# alphanewt_v1_7.net
KiCad netlist of a schematic drawn in EAGLE
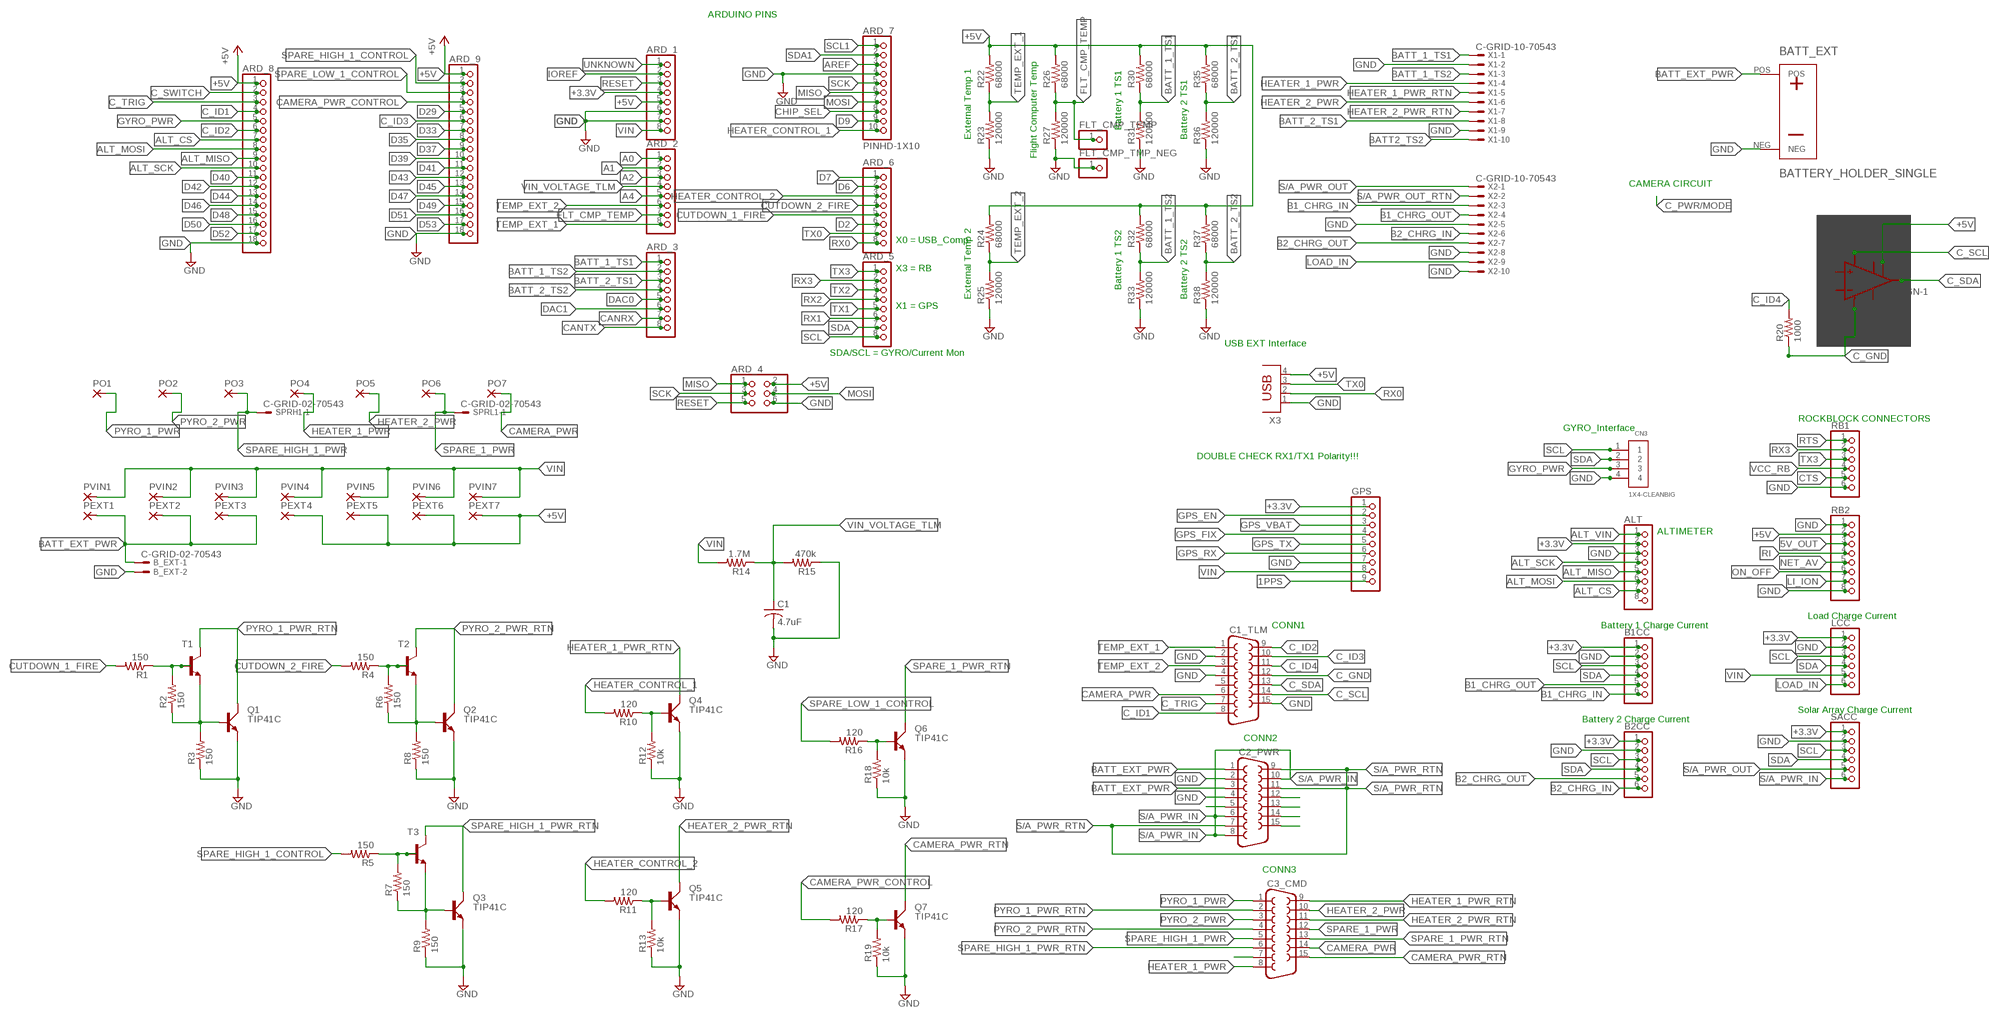
[diagram p0: schematic, sheet 1]

(export (version "E")
  (design (tool "Eeschema 10.0.6"))
  (components
    (comp (ref "ALT")
      (value "PINHD-1X8BIG")
      (footprint "eagle-import:1X08-BIG")
      (libsource (lib "eagle-import") (part "PINHD-1X8BIG"))
    )
    (comp (ref "ARD_1")
      (value "PINHD-1X8BIG")
      (footprint "eagle-import:1X08-BIG")
      (libsource (lib "eagle-import") (part "PINHD-1X8BIG"))
    )
    (comp (ref "ARD_2")
      (value "PINHD-1X8BIG")
      (footprint "eagle-import:1X08-BIG")
      (libsource (lib "eagle-import") (part "PINHD-1X8BIG"))
    )
    (comp (ref "ARD_3")
      (value "PINHD-1X8BIG")
      (footprint "eagle-import:1X08-BIG")
      (libsource (lib "eagle-import") (part "PINHD-1X8BIG"))
    )
    (comp (ref "ARD_4")
      (value "PINHD-2X3")
      (footprint "eagle-import:2X03")
      (libsource (lib "eagle-import") (part "PINHD-2X3"))
    )
    (comp (ref "ARD_5")
      (value "PINHD-1X8BIG")
      (footprint "eagle-import:1X08-BIG")
      (libsource (lib "eagle-import") (part "PINHD-1X8BIG"))
    )
    (comp (ref "ARD_6")
      (value "PINHD-1X8BIG")
      (footprint "eagle-import:1X08-BIG")
      (libsource (lib "eagle-import") (part "PINHD-1X8BIG"))
    )
    (comp (ref "ARD_7")
      (value "PINHD-1X10")
      (footprint "eagle-import:1X10-BIG")
      (libsource (lib "eagle-import") (part "PINHD-1X10"))
    )
    (comp (ref "ARD_8")
      (value "PINHD-1X18-BIG")
      (footprint "eagle-import:1X18-BIG")
      (libsource (lib "eagle-import") (part "PINHD-1X18-BIG"))
    )
    (comp (ref "ARD_9")
      (value "PINHD-1X18-BIG")
      (footprint "eagle-import:1X18-BIG")
      (libsource (lib "eagle-import") (part "PINHD-1X18-BIG"))
    )
    (comp (ref "B1CC")
      (value "PINHD-1X6B")
      (footprint "eagle-import:1X06-BIG")
      (libsource (lib "eagle-import") (part "PINHD-1X6B"))
    )
    (comp (ref "B2CC")
      (value "PINHD-1X6B")
      (footprint "eagle-import:1X06-BIG")
      (libsource (lib "eagle-import") (part "PINHD-1X6B"))
    )
    (comp (ref "BATT_EXT")
      (value "BATTERY_HOLDER_SINGLE")
      (footprint "eagle-import:BATT_HOLDER_SINGLE")
      (libsource (lib "eagle-import") (part "BATTERY_HOLDER_SINGLE"))
    )
    (comp (ref "B_EXT")
      (value "C-GRID-02-70543")
      (footprint "eagle-import:70543-02")
      (fields
        (field (name "MF") "MOLEX")
        (field (name "MPN") "70543-0001")
        (field (name "OC_NEWARK") "59H2645")
      )
      (libsource (lib "eagle-import") (part "C-GRID-02-70543"))
    )
    (comp (ref "C1")
      (value "4.7uF")
      (footprint "eagle-import:C0805K")
      (fields (field (name "MPN") "C2012X6S1H475K125AC"))
      (libsource (lib "eagle-import") (part "C-USC0805K"))
    )
    (comp (ref "C1_TLM")
      (value "F15HP")
      (footprint "eagle-import:F15HP")
      (fields (field (name "MPN") "5504F1-15S-02A-03"))
      (libsource (lib "eagle-import") (part "F15HP"))
    )
    (comp (ref "C2_PWR")
      (value "F15HP")
      (footprint "eagle-import:F15HP")
      (fields (field (name "MPN") "5504F1-15S-02A-03"))
      (libsource (lib "eagle-import") (part "F15HP"))
    )
    (comp (ref "C3_CMD")
      (value "F15HP")
      (footprint "eagle-import:F15HP")
      (fields (field (name "MPN") "5504F1-15S-02A-03"))
      (libsource (lib "eagle-import") (part "F15HP"))
    )
    (comp (ref "CN3")
      (value "1X4-CLEANBIG")
      (footprint "eagle-import:1X04-CLEANBIG")
      (libsource (lib "eagle-import") (part "1X4-CLEANBIG"))
    )
    (comp (ref "FLT_CMP_TEMP")
      (value "PINHD-1X1")
      (footprint "eagle-import:1X01")
      (libsource (lib "eagle-import") (part "PINHD-1X1"))
    )
    (comp (ref "FLT_CMP_TMP_NEG")
      (value "PINHD-1X1")
      (footprint "eagle-import:1X01")
      (libsource (lib "eagle-import") (part "PINHD-1X1"))
    )
    (comp (ref "GPS")
      (value "PINHD-1X9")
      (footprint "eagle-import:1X09-BIG")
      (libsource (lib "eagle-import") (part "PINHD-1X9"))
    )
    (comp (ref "IC1")
      (value "LM386N-1")
      (footprint "eagle-import:DIL08")
      (libsource (lib "eagle-import") (part "LM386?-N1"))
    )
    (comp (ref "LCC")
      (value "PINHD-1X6B")
      (footprint "eagle-import:1X06-BIG")
      (libsource (lib "eagle-import") (part "PINHD-1X6B"))
    )
    (comp (ref "PEXT1")
      (value "SMD2")
      (footprint "eagle-import:SMD1,27-2,54")
      (libsource (lib "eagle-import") (part "SMD2"))
    )
    (comp (ref "PEXT2")
      (value "SMD2")
      (footprint "eagle-import:SMD1,27-2,54")
      (libsource (lib "eagle-import") (part "SMD2"))
    )
    (comp (ref "PEXT3")
      (value "SMD2")
      (footprint "eagle-import:SMD1,27-2,54")
      (libsource (lib "eagle-import") (part "SMD2"))
    )
    (comp (ref "PEXT4")
      (value "SMD2")
      (footprint "eagle-import:SMD1,27-2,54")
      (libsource (lib "eagle-import") (part "SMD2"))
    )
    (comp (ref "PEXT5")
      (value "SMD2")
      (footprint "eagle-import:SMD1,27-2,54")
      (libsource (lib "eagle-import") (part "SMD2"))
    )
    (comp (ref "PEXT6")
      (value "SMD2")
      (footprint "eagle-import:SMD1,27-2,54")
      (libsource (lib "eagle-import") (part "SMD2"))
    )
    (comp (ref "PEXT7")
      (value "SMD2")
      (footprint "eagle-import:SMD1,27-2,54")
      (libsource (lib "eagle-import") (part "SMD2"))
    )
    (comp (ref "PO1")
      (value "SMD2")
      (footprint "eagle-import:SMD1,27-2,54")
      (libsource (lib "eagle-import") (part "SMD2"))
    )
    (comp (ref "PO2")
      (value "SMD2")
      (footprint "eagle-import:SMD1,27-2,54")
      (libsource (lib "eagle-import") (part "SMD2"))
    )
    (comp (ref "PO3")
      (value "SMD2")
      (footprint "eagle-import:SMD1,27-2,54")
      (libsource (lib "eagle-import") (part "SMD2"))
    )
    (comp (ref "PO4")
      (value "SMD2")
      (footprint "eagle-import:SMD1,27-2,54")
      (libsource (lib "eagle-import") (part "SMD2"))
    )
    (comp (ref "PO5")
      (value "SMD2")
      (footprint "eagle-import:SMD1,27-2,54")
      (libsource (lib "eagle-import") (part "SMD2"))
    )
    (comp (ref "PO6")
      (value "SMD2")
      (footprint "eagle-import:SMD1,27-2,54")
      (libsource (lib "eagle-import") (part "SMD2"))
    )
    (comp (ref "PO7")
      (value "SMD2")
      (footprint "eagle-import:SMD1,27-2,54")
      (libsource (lib "eagle-import") (part "SMD2"))
    )
    (comp (ref "PVIN1")
      (value "SMD2")
      (footprint "eagle-import:SMD1,27-2,54")
      (libsource (lib "eagle-import") (part "SMD2"))
    )
    (comp (ref "PVIN2")
      (value "SMD2")
      (footprint "eagle-import:SMD1,27-2,54")
      (libsource (lib "eagle-import") (part "SMD2"))
    )
    (comp (ref "PVIN3")
      (value "SMD2")
      (footprint "eagle-import:SMD1,27-2,54")
      (libsource (lib "eagle-import") (part "SMD2"))
    )
    (comp (ref "PVIN4")
      (value "SMD2")
      (footprint "eagle-import:SMD1,27-2,54")
      (libsource (lib "eagle-import") (part "SMD2"))
    )
    (comp (ref "PVIN5")
      (value "SMD2")
      (footprint "eagle-import:SMD1,27-2,54")
      (libsource (lib "eagle-import") (part "SMD2"))
    )
    (comp (ref "PVIN6")
      (value "SMD2")
      (footprint "eagle-import:SMD1,27-2,54")
      (libsource (lib "eagle-import") (part "SMD2"))
    )
    (comp (ref "PVIN7")
      (value "SMD2")
      (footprint "eagle-import:SMD1,27-2,54")
      (libsource (lib "eagle-import") (part "SMD2"))
    )
    (comp (ref "Q1")
      (value "TIP41C")
      (footprint "eagle-import:TO220AV")
      (fields (field (name "MF") "FAIRCHILD SEMICONDUCTOR"))
      (libsource (lib "eagle-import") (part "TIP41C"))
    )
    (comp (ref "Q2")
      (value "TIP41C")
      (footprint "eagle-import:TO220AV")
      (fields (field (name "MF") "FAIRCHILD SEMICONDUCTOR"))
      (libsource (lib "eagle-import") (part "TIP41C"))
    )
    (comp (ref "Q3")
      (value "TIP41C")
      (footprint "eagle-import:TO220AV")
      (fields (field (name "MF") "FAIRCHILD SEMICONDUCTOR"))
      (libsource (lib "eagle-import") (part "TIP41C"))
    )
    (comp (ref "Q4")
      (value "TIP41C")
      (footprint "eagle-import:TO220AV")
      (fields (field (name "MF") "FAIRCHILD SEMICONDUCTOR"))
      (libsource (lib "eagle-import") (part "TIP41C"))
    )
    (comp (ref "Q5")
      (value "TIP41C")
      (footprint "eagle-import:TO220AV")
      (fields (field (name "MF") "FAIRCHILD SEMICONDUCTOR"))
      (libsource (lib "eagle-import") (part "TIP41C"))
    )
    (comp (ref "Q6")
      (value "TIP41C")
      (footprint "eagle-import:TO220AV")
      (fields (field (name "MF") "FAIRCHILD SEMICONDUCTOR"))
      (libsource (lib "eagle-import") (part "TIP41C"))
    )
    (comp (ref "Q7")
      (value "TIP41C")
      (footprint "eagle-import:TO220AV")
      (fields (field (name "MF") "FAIRCHILD SEMICONDUCTOR"))
      (libsource (lib "eagle-import") (part "TIP41C"))
    )
    (comp (ref "R1")
      (value "150")
      (footprint "eagle-import:R0805")
      (fields (field (name "MF") "VISHAY/DALE") (field (name "MPN") "CRCW120633R2FKEA"))
      (libsource (lib "eagle-import") (part "R-US_R0805"))
    )
    (comp (ref "R2")
      (value "150")
      (footprint "eagle-import:R0805")
      (fields (field (name "MF") "VISHAY/DALE") (field (name "MPN") "CRCW120633R2FKEA"))
      (libsource (lib "eagle-import") (part "R-US_R0805"))
    )
    (comp (ref "R3")
      (value "150")
      (footprint "eagle-import:R0805")
      (fields (field (name "MF") "VISHAY/DALE") (field (name "MPN") "CRCW120633R2FKEA"))
      (libsource (lib "eagle-import") (part "R-US_R0805"))
    )
    (comp (ref "R4")
      (value "150")
      (footprint "eagle-import:R0805")
      (fields (field (name "MF") "VISHAY/DALE") (field (name "MPN") "CRCW120633R2FKEA"))
      (libsource (lib "eagle-import") (part "R-US_R0805"))
    )
    (comp (ref "R5")
      (value "150")
      (footprint "eagle-import:R0805")
      (fields (field (name "MF") "VISHAY/DALE") (field (name "MPN") "CRCW120633R2FKEA"))
      (libsource (lib "eagle-import") (part "R-US_R0805"))
    )
    (comp (ref "R6")
      (value "150")
      (footprint "eagle-import:R0805")
      (fields (field (name "MF") "VISHAY/DALE") (field (name "MPN") "CRCW120633R2FKEA"))
      (libsource (lib "eagle-import") (part "R-US_R0805"))
    )
    (comp (ref "R7")
      (value "150")
      (footprint "eagle-import:R0805")
      (fields (field (name "MF") "VISHAY/DALE") (field (name "MPN") "CRCW120633R2FKEA"))
      (libsource (lib "eagle-import") (part "R-US_R0805"))
    )
    (comp (ref "R8")
      (value "150")
      (footprint "eagle-import:R0805")
      (fields (field (name "MF") "VISHAY/DALE") (field (name "MPN") "CRCW120633R2FKEA"))
      (libsource (lib "eagle-import") (part "R-US_R0805"))
    )
    (comp (ref "R9")
      (value "150")
      (footprint "eagle-import:R0805")
      (fields (field (name "MF") "VISHAY/DALE") (field (name "MPN") "CRCW120633R2FKEA"))
      (libsource (lib "eagle-import") (part "R-US_R0805"))
    )
    (comp (ref "R10")
      (value "120")
      (footprint "eagle-import:R0805")
      (fields (field (name "MF") "VISHAY/DALE") (field (name "MPN") "CRCW120633R2FKEA"))
      (libsource (lib "eagle-import") (part "R-US_R0805"))
    )
    (comp (ref "R11")
      (value "120")
      (footprint "eagle-import:R0805")
      (fields (field (name "MF") "VISHAY/DALE") (field (name "MPN") "CRCW120633R2FKEA"))
      (libsource (lib "eagle-import") (part "R-US_R0805"))
    )
    (comp (ref "R12")
      (value "10k")
      (footprint "eagle-import:R0805")
      (fields (field (name "MF") "VISHAY/DALE") (field (name "MPN") "CRCW120633R2FKEA"))
      (libsource (lib "eagle-import") (part "R-US_R0805"))
    )
    (comp (ref "R13")
      (value "10k")
      (footprint "eagle-import:R0805")
      (fields (field (name "MF") "VISHAY/DALE") (field (name "MPN") "CRCW120633R2FKEA"))
      (libsource (lib "eagle-import") (part "R-US_R0805"))
    )
    (comp (ref "R14")
      (value "1.7M")
      (footprint "eagle-import:R0805")
      (fields (field (name "MF") "VISHAY/DALE") (field (name "MPN") "CRCW120633R2FKEA"))
      (libsource (lib "eagle-import") (part "R-US_R0805"))
    )
    (comp (ref "R15")
      (value "470k")
      (footprint "eagle-import:R0805")
      (fields (field (name "MF") "VISHAY/DALE") (field (name "MPN") "CRCW120633R2FKEA"))
      (libsource (lib "eagle-import") (part "R-US_R0805"))
    )
    (comp (ref "R16")
      (value "120")
      (footprint "eagle-import:R0805")
      (fields (field (name "MF") "VISHAY/DALE") (field (name "MPN") "CRCW120633R2FKEA"))
      (libsource (lib "eagle-import") (part "R-US_R0805"))
    )
    (comp (ref "R17")
      (value "120")
      (footprint "eagle-import:R0805")
      (fields (field (name "MF") "VISHAY/DALE") (field (name "MPN") "CRCW120633R2FKEA"))
      (libsource (lib "eagle-import") (part "R-US_R0805"))
    )
    (comp (ref "R18")
      (value "10k")
      (footprint "eagle-import:R0805")
      (fields (field (name "MF") "VISHAY/DALE") (field (name "MPN") "CRCW120633R2FKEA"))
      (libsource (lib "eagle-import") (part "R-US_R0805"))
    )
    (comp (ref "R19")
      (value "10k")
      (footprint "eagle-import:R0805")
      (fields (field (name "MF") "VISHAY/DALE") (field (name "MPN") "CRCW120633R2FKEA"))
      (libsource (lib "eagle-import") (part "R-US_R0805"))
    )
    (comp (ref "R20")
      (value "1000")
      (footprint "eagle-import:R0805")
      (fields (field (name "MF") "VISHAY/DALE") (field (name "MPN") "CRCW120633R2FKEA"))
      (libsource (lib "eagle-import") (part "R-US_R0805"))
    )
    (comp (ref "R22")
      (value "68000")
      (footprint "eagle-import:R0805")
      (fields (field (name "MF") "VISHAY/DALE") (field (name "MPN") "CRCW120633R2FKEA"))
      (libsource (lib "eagle-import") (part "R-US_R0805"))
    )
    (comp (ref "R23")
      (value "120000")
      (footprint "eagle-import:R0805")
      (fields (field (name "MF") "VISHAY/DALE") (field (name "MPN") "CRCW120633R2FKEA"))
      (libsource (lib "eagle-import") (part "R-US_R0805"))
    )
    (comp (ref "R24")
      (value "68000")
      (footprint "eagle-import:R0805")
      (fields (field (name "MF") "VISHAY/DALE") (field (name "MPN") "CRCW120633R2FKEA"))
      (libsource (lib "eagle-import") (part "R-US_R0805"))
    )
    (comp (ref "R25")
      (value "120000")
      (footprint "eagle-import:R0805")
      (fields (field (name "MF") "VISHAY/DALE") (field (name "MPN") "CRCW120633R2FKEA"))
      (libsource (lib "eagle-import") (part "R-US_R0805"))
    )
    (comp (ref "R26")
      (value "68000")
      (footprint "eagle-import:R0805")
      (fields (field (name "MF") "VISHAY/DALE") (field (name "MPN") "CRCW120633R2FKEA"))
      (libsource (lib "eagle-import") (part "R-US_R0805"))
    )
    (comp (ref "R27")
      (value "120000")
      (footprint "eagle-import:R0805")
      (fields (field (name "MF") "VISHAY/DALE") (field (name "MPN") "CRCW120633R2FKEA"))
      (libsource (lib "eagle-import") (part "R-US_R0805"))
    )
    (comp (ref "R30")
      (value "68000")
      (footprint "eagle-import:R0805")
      (fields (field (name "MF") "VISHAY/DALE") (field (name "MPN") "CRCW120633R2FKEA"))
      (libsource (lib "eagle-import") (part "R-US_R0805"))
    )
    (comp (ref "R31")
      (value "120000")
      (footprint "eagle-import:R0805")
      (fields (field (name "MF") "VISHAY/DALE") (field (name "MPN") "CRCW120633R2FKEA"))
      (libsource (lib "eagle-import") (part "R-US_R0805"))
    )
    (comp (ref "R32")
      (value "68000")
      (footprint "eagle-import:R0805")
      (fields (field (name "MF") "VISHAY/DALE") (field (name "MPN") "CRCW120633R2FKEA"))
      (libsource (lib "eagle-import") (part "R-US_R0805"))
    )
    (comp (ref "R33")
      (value "120000")
      (footprint "eagle-import:R0805")
      (fields (field (name "MF") "VISHAY/DALE") (field (name "MPN") "CRCW120633R2FKEA"))
      (libsource (lib "eagle-import") (part "R-US_R0805"))
    )
    (comp (ref "R35")
      (value "68000")
      (footprint "eagle-import:R0805")
      (fields (field (name "MF") "VISHAY/DALE") (field (name "MPN") "CRCW120633R2FKEA"))
      (libsource (lib "eagle-import") (part "R-US_R0805"))
    )
    (comp (ref "R36")
      (value "120000")
      (footprint "eagle-import:R0805")
      (fields (field (name "MF") "VISHAY/DALE") (field (name "MPN") "CRCW120633R2FKEA"))
      (libsource (lib "eagle-import") (part "R-US_R0805"))
    )
    (comp (ref "R37")
      (value "68000")
      (footprint "eagle-import:R0805")
      (fields (field (name "MF") "VISHAY/DALE") (field (name "MPN") "CRCW120633R2FKEA"))
      (libsource (lib "eagle-import") (part "R-US_R0805"))
    )
    (comp (ref "R38")
      (value "120000")
      (footprint "eagle-import:R0805")
      (fields (field (name "MF") "VISHAY/DALE") (field (name "MPN") "CRCW120633R2FKEA"))
      (libsource (lib "eagle-import") (part "R-US_R0805"))
    )
    (comp (ref "RB1")
      (value "PINHD-1X6CB")
      (footprint "eagle-import:1X06-CLEANBIG")
      (libsource (lib "eagle-import") (part "PINHD-1X6CB"))
    )
    (comp (ref "RB2")
      (value "PINHD-1X8BIG")
      (footprint "eagle-import:1X08-BIG")
      (libsource (lib "eagle-import") (part "PINHD-1X8BIG"))
    )
    (comp (ref "SACC")
      (value "PINHD-1X6B")
      (footprint "eagle-import:1X06-BIG")
      (libsource (lib "eagle-import") (part "PINHD-1X6B"))
    )
    (comp (ref "SPRH1")
      (value "C-GRID-02-70543")
      (footprint "eagle-import:70543-02")
      (fields
        (field (name "MF") "MOLEX")
        (field (name "MPN") "70543-0001")
        (field (name "OC_NEWARK") "59H2645")
      )
      (libsource (lib "eagle-import") (part "C-GRID-02-70543"))
    )
    (comp (ref "SPRL1")
      (value "C-GRID-02-70543")
      (footprint "eagle-import:70543-02")
      (fields
        (field (name "MF") "MOLEX")
        (field (name "MPN") "70543-0001")
        (field (name "OC_NEWARK") "59H2645")
      )
      (libsource (lib "eagle-import") (part "C-GRID-02-70543"))
    )
    (comp (ref "T1")
      (value "2N3904")
      (footprint "eagle-import:TO92")
      (fields (field (name "MF") "NTE ELECTRONICS"))
      (libsource (lib "eagle-import") (part "2N3904"))
    )
    (comp (ref "T2")
      (value "2N3904")
      (footprint "eagle-import:TO92")
      (fields (field (name "MF") "NTE ELECTRONICS"))
      (libsource (lib "eagle-import") (part "2N3904"))
    )
    (comp (ref "T3")
      (value "2N3904")
      (footprint "eagle-import:TO92")
      (fields (field (name "MF") "NTE ELECTRONICS"))
      (libsource (lib "eagle-import") (part "2N3904"))
    )
    (comp (ref "X1")
      (value "C-GRID-10-70543")
      (footprint "eagle-import:70543-10")
      (libsource (lib "eagle-import") (part "C-GRID-10-70543"))
    )
    (comp (ref "X2")
      (value "C-GRID-10-70543")
      (footprint "eagle-import:70543-10")
      (libsource (lib "eagle-import") (part "C-GRID-10-70543"))
    )
    (comp (ref "X3")
      (value "PN87520")
      (footprint "eagle-import:PN87520")
      (libsource (lib "eagle-import") (part "PN87520"))
    )
  )
  (nets
    (net (code "1") (name "+3.3V") (class "Default")
      (node (ref "ALT") (pin "2") (pinfunction "2_2") (pintype "passive"))
      (node (ref "ARD_1") (pin "4") (pinfunction "4_4") (pintype "passive"))
      (node (ref "B1CC") (pin "1") (pinfunction "1_1") (pintype "passive"))
      (node (ref "B2CC") (pin "1") (pinfunction "1_1") (pintype "passive"))
      (node (ref "GPS") (pin "1") (pinfunction "1_1") (pintype "passive"))
      (node (ref "LCC") (pin "1") (pinfunction "1_1") (pintype "passive"))
      (node (ref "SACC") (pin "1") (pinfunction "1_1") (pintype "passive"))
    )
    (net (code "2") (name "+5V") (class "Default")
      (node (ref "ARD_1") (pin "5") (pinfunction "5_5") (pintype "passive"))
      (node (ref "ARD_4") (pin "2") (pinfunction "2_2") (pintype "passive"))
      (node (ref "ARD_8") (pin "1") (pinfunction "1_1") (pintype "passive"))
      (node (ref "ARD_9") (pin "1") (pinfunction "1_1") (pintype "passive"))
      (node (ref "IC1") (pin "8") (pinfunction "GAIN_8") (pintype "passive"))
      (node (ref "PEXT4") (pin "1") (pinfunction "P_1") (pintype "passive"))
      (node (ref "PEXT5") (pin "1") (pinfunction "P_1") (pintype "passive"))
      (node (ref "PEXT6") (pin "1") (pinfunction "P_1") (pintype "passive"))
      (node (ref "PEXT7") (pin "1") (pinfunction "P_1") (pintype "passive"))
      (node (ref "R22") (pin "2") (pinfunction "2_2") (pintype "passive"))
      (node (ref "R24") (pin "2") (pinfunction "2_2") (pintype "passive"))
      (node (ref "R26") (pin "2") (pinfunction "2_2") (pintype "passive"))
      (node (ref "R30") (pin "2") (pinfunction "2_2") (pintype "passive"))
      (node (ref "R32") (pin "2") (pinfunction "2_2") (pintype "passive"))
      (node (ref "R35") (pin "2") (pinfunction "2_2") (pintype "passive"))
      (node (ref "R37") (pin "2") (pinfunction "2_2") (pintype "passive"))
      (node (ref "RB2") (pin "2") (pinfunction "2_2") (pintype "passive"))
      (node (ref "X3") (pin "4") (pinfunction "4_4") (pintype "passive"))
    )
    (net (code "3") (name "1PPS") (class "Default")
      (node (ref "GPS") (pin "9") (pinfunction "9_9") (pintype "passive"))
    )
    (net (code "4") (name "5V_OUT") (class "Default")
      (node (ref "RB2") (pin "3") (pinfunction "3_3") (pintype "passive"))
    )
    (net (code "5") (name "A0") (class "Default")
      (node (ref "ARD_2") (pin "1") (pinfunction "1_1") (pintype "passive"))
    )
    (net (code "6") (name "A1") (class "Default")
      (node (ref "ARD_2") (pin "2") (pinfunction "2_2") (pintype "passive"))
    )
    (net (code "7") (name "A2") (class "Default")
      (node (ref "ARD_2") (pin "3") (pinfunction "3_3") (pintype "passive"))
    )
    (net (code "8") (name "A4") (class "Default")
      (node (ref "ARD_2") (pin "5") (pinfunction "5_5") (pintype "passive"))
    )
    (net (code "9") (name "ALT_CS") (class "Default")
      (node (ref "ALT") (pin "7") (pinfunction "7_7") (pintype "passive"))
      (node (ref "ARD_8") (pin "7") (pinfunction "7_7") (pintype "passive"))
    )
    (net (code "10") (name "ALT_MISO") (class "Default")
      (node (ref "ALT") (pin "5") (pinfunction "5_5") (pintype "passive"))
      (node (ref "ARD_8") (pin "9") (pinfunction "9_9") (pintype "passive"))
    )
    (net (code "11") (name "ALT_MOSI") (class "Default")
      (node (ref "ALT") (pin "6") (pinfunction "6_6") (pintype "passive"))
      (node (ref "ARD_8") (pin "8") (pinfunction "8_8") (pintype "passive"))
    )
    (net (code "12") (name "ALT_SCK") (class "Default")
      (node (ref "ALT") (pin "4") (pinfunction "4_4") (pintype "passive"))
      (node (ref "ARD_8") (pin "10") (pinfunction "10_10") (pintype "passive"))
    )
    (net (code "13") (name "ALT_VIN") (class "Default")
      (node (ref "ALT") (pin "1") (pinfunction "1_1") (pintype "passive"))
    )
    (net (code "14") (name "AREF") (class "Default")
      (node (ref "ARD_7") (pin "3") (pinfunction "3_3") (pintype "passive"))
    )
    (net (code "15") (name "B1_CHRG_IN") (class "Default")
      (node (ref "B1CC") (pin "6") (pinfunction "6_6") (pintype "passive"))
      (node (ref "X2") (pin "3") (pinfunction "S_3") (pintype "passive"))
    )
    (net (code "16") (name "B1_CHRG_OUT") (class "Default")
      (node (ref "B1CC") (pin "5") (pinfunction "5_5") (pintype "passive"))
      (node (ref "X2") (pin "4") (pinfunction "S_4") (pintype "passive"))
    )
    (net (code "17") (name "B2_CHRG_IN") (class "Default")
      (node (ref "B2CC") (pin "6") (pinfunction "6_6") (pintype "passive"))
      (node (ref "X2") (pin "6") (pinfunction "S_6") (pintype "passive"))
    )
    (net (code "18") (name "B2_CHRG_OUT") (class "Default")
      (node (ref "B2CC") (pin "5") (pinfunction "5_5") (pintype "passive"))
      (node (ref "X2") (pin "7") (pinfunction "S_7") (pintype "passive"))
    )
    (net (code "19") (name "BATT2_TS2") (class "Default")
      (node (ref "X1") (pin "10") (pinfunction "S_10") (pintype "passive"))
    )
    (net (code "20") (name "BATT_1_TS1") (class "Default")
      (node (ref "ARD_3") (pin "1") (pinfunction "1_1") (pintype "passive"))
      (node (ref "R30") (pin "1") (pinfunction "1_1") (pintype "passive"))
      (node (ref "R31") (pin "2") (pinfunction "2_2") (pintype "passive"))
      (node (ref "X1") (pin "1") (pinfunction "S_1") (pintype "passive"))
    )
    (net (code "21") (name "BATT_1_TS2") (class "Default")
      (node (ref "ARD_3") (pin "2") (pinfunction "2_2") (pintype "passive"))
      (node (ref "R32") (pin "1") (pinfunction "1_1") (pintype "passive"))
      (node (ref "R33") (pin "2") (pinfunction "2_2") (pintype "passive"))
      (node (ref "X1") (pin "3") (pinfunction "S_3") (pintype "passive"))
    )
    (net (code "22") (name "BATT_2_TS1") (class "Default")
      (node (ref "ARD_3") (pin "3") (pinfunction "3_3") (pintype "passive"))
      (node (ref "R35") (pin "1") (pinfunction "1_1") (pintype "passive"))
      (node (ref "R36") (pin "2") (pinfunction "2_2") (pintype "passive"))
      (node (ref "X1") (pin "8") (pinfunction "S_8") (pintype "passive"))
    )
    (net (code "23") (name "BATT_2_TS2") (class "Default")
      (node (ref "ARD_3") (pin "4") (pinfunction "4_4") (pintype "passive"))
      (node (ref "R37") (pin "1") (pinfunction "1_1") (pintype "passive"))
      (node (ref "R38") (pin "2") (pinfunction "2_2") (pintype "passive"))
    )
    (net (code "24") (name "BATT_EXT_PWR") (class "Default")
      (node (ref "BATT_EXT") (pin "POS") (pinfunction "POS_POS") (pintype "bidirectional"))
      (node (ref "B_EXT") (pin "1") (pinfunction "S_1") (pintype "passive"))
      (node (ref "C2_PWR") (pin "1") (pinfunction "1_1") (pintype "passive"))
      (node (ref "C2_PWR") (pin "3") (pinfunction "3_3") (pintype "passive"))
      (node (ref "PEXT1") (pin "1") (pinfunction "P_1") (pintype "passive"))
      (node (ref "PEXT2") (pin "1") (pinfunction "P_1") (pintype "passive"))
      (node (ref "PEXT3") (pin "1") (pinfunction "P_1") (pintype "passive"))
    )
    (net (code "25") (name "CAMERA_PWR") (class "Default")
      (node (ref "C1_TLM") (pin "6") (pinfunction "6_6") (pintype "passive"))
      (node (ref "C3_CMD") (pin "14") (pinfunction "14_14") (pintype "passive"))
      (node (ref "PO7") (pin "1") (pinfunction "P_1") (pintype "passive"))
    )
    (net (code "26") (name "CAMERA_PWR_CONTROL") (class "Default")
      (node (ref "ARD_9") (pin "4") (pinfunction "4_4") (pintype "passive"))
      (node (ref "R17") (pin "2") (pinfunction "2_2") (pintype "passive"))
    )
    (net (code "27") (name "CAMERA_PWR_RTN") (class "Default")
      (node (ref "C3_CMD") (pin "15") (pinfunction "15_15") (pintype "passive"))
      (node (ref "Q7") (pin "C") (pinfunction "C_C") (pintype "passive"))
    )
    (net (code "28") (name "CANRX") (class "Default")
      (node (ref "ARD_3") (pin "7") (pinfunction "7_7") (pintype "passive"))
    )
    (net (code "29") (name "CANTX") (class "Default")
      (node (ref "ARD_3") (pin "8") (pinfunction "8_8") (pintype "passive"))
    )
    (net (code "30") (name "CHIP_SEL") (class "Default")
      (node (ref "ARD_7") (pin "8") (pinfunction "8_8") (pintype "passive"))
    )
    (net (code "31") (name "CTS") (class "Default")
      (node (ref "RB1") (pin "5") (pinfunction "5_5") (pintype "passive"))
    )
    (net (code "32") (name "CUTDOWN_1_FIRE") (class "Default")
      (node (ref "ARD_6") (pin "5") (pinfunction "5_5") (pintype "passive"))
      (node (ref "R1") (pin "2") (pinfunction "2_2") (pintype "passive"))
    )
    (net (code "33") (name "CUTDOWN_2_FIRE") (class "Default")
      (node (ref "ARD_6") (pin "4") (pinfunction "4_4") (pintype "passive"))
      (node (ref "R4") (pin "2") (pinfunction "2_2") (pintype "passive"))
    )
    (net (code "34") (name "C_GND") (class "Default")
      (node (ref "C1_TLM") (pin "12") (pinfunction "12_12") (pintype "passive"))
      (node (ref "IC1") (pin "4") (pinfunction "GND_4") (pintype "power_in"))
      (node (ref "R20") (pin "1") (pinfunction "1_1") (pintype "passive"))
    )
    (net (code "35") (name "C_ID1") (class "Default")
      (node (ref "ARD_8") (pin "4") (pinfunction "4_4") (pintype "passive"))
      (node (ref "C1_TLM") (pin "8") (pinfunction "8_8") (pintype "passive"))
    )
    (net (code "36") (name "C_ID2") (class "Default")
      (node (ref "ARD_8") (pin "6") (pinfunction "6_6") (pintype "passive"))
      (node (ref "C1_TLM") (pin "9") (pinfunction "9_9") (pintype "passive"))
    )
    (net (code "37") (name "C_ID3") (class "Default")
      (node (ref "ARD_9") (pin "6") (pinfunction "6_6") (pintype "passive"))
      (node (ref "C1_TLM") (pin "10") (pinfunction "10_10") (pintype "passive"))
    )
    (net (code "38") (name "C_ID4") (class "Default")
      (node (ref "C1_TLM") (pin "11") (pinfunction "11_11") (pintype "passive"))
      (node (ref "R20") (pin "2") (pinfunction "2_2") (pintype "passive"))
    )
    (net (code "40") (name "C_SCL") (class "Default")
      (node (ref "C1_TLM") (pin "14") (pinfunction "14_14") (pintype "passive"))
      (node (ref "IC1") (pin "6") (pinfunction "VS_6") (pintype "power_in"))
    )
    (net (code "41") (name "C_SDA") (class "Default")
      (node (ref "C1_TLM") (pin "13") (pinfunction "13_13") (pintype "passive"))
      (node (ref "IC1") (pin "5") (pinfunction "OUT_5") (pintype "output"))
    )
    (net (code "42") (name "C_SWITCH") (class "Default")
      (node (ref "ARD_8") (pin "2") (pinfunction "2_2") (pintype "passive"))
    )
    (net (code "43") (name "C_TRIG") (class "Default")
      (node (ref "ARD_8") (pin "3") (pinfunction "3_3") (pintype "passive"))
      (node (ref "C1_TLM") (pin "7") (pinfunction "7_7") (pintype "passive"))
    )
    (net (code "44") (name "D2") (class "Default")
      (node (ref "ARD_6") (pin "6") (pinfunction "6_6") (pintype "passive"))
    )
    (net (code "45") (name "D6") (class "Default")
      (node (ref "ARD_6") (pin "2") (pinfunction "2_2") (pintype "passive"))
    )
    (net (code "46") (name "D7") (class "Default")
      (node (ref "ARD_6") (pin "1") (pinfunction "1_1") (pintype "passive"))
    )
    (net (code "47") (name "D9") (class "Default")
      (node (ref "ARD_7") (pin "9") (pinfunction "9_9") (pintype "passive"))
    )
    (net (code "48") (name "D29") (class "Default")
      (node (ref "ARD_9") (pin "5") (pinfunction "5_5") (pintype "passive"))
    )
    (net (code "49") (name "D33") (class "Default")
      (node (ref "ARD_9") (pin "7") (pinfunction "7_7") (pintype "passive"))
    )
    (net (code "50") (name "D35") (class "Default")
      (node (ref "ARD_9") (pin "8") (pinfunction "8_8") (pintype "passive"))
    )
    (net (code "51") (name "D37") (class "Default")
      (node (ref "ARD_9") (pin "9") (pinfunction "9_9") (pintype "passive"))
    )
    (net (code "52") (name "D39") (class "Default")
      (node (ref "ARD_9") (pin "10") (pinfunction "10_10") (pintype "passive"))
    )
    (net (code "53") (name "D40") (class "Default")
      (node (ref "ARD_8") (pin "11") (pinfunction "11_11") (pintype "passive"))
    )
    (net (code "54") (name "D41") (class "Default")
      (node (ref "ARD_9") (pin "11") (pinfunction "11_11") (pintype "passive"))
    )
    (net (code "55") (name "D42") (class "Default")
      (node (ref "ARD_8") (pin "12") (pinfunction "12_12") (pintype "passive"))
    )
    (net (code "56") (name "D43") (class "Default")
      (node (ref "ARD_9") (pin "12") (pinfunction "12_12") (pintype "passive"))
    )
    (net (code "57") (name "D44") (class "Default")
      (node (ref "ARD_8") (pin "13") (pinfunction "13_13") (pintype "passive"))
    )
    (net (code "58") (name "D45") (class "Default")
      (node (ref "ARD_9") (pin "13") (pinfunction "13_13") (pintype "passive"))
    )
    (net (code "59") (name "D46") (class "Default")
      (node (ref "ARD_8") (pin "14") (pinfunction "14_14") (pintype "passive"))
    )
    (net (code "60") (name "D47") (class "Default")
      (node (ref "ARD_9") (pin "14") (pinfunction "14_14") (pintype "passive"))
    )
    (net (code "61") (name "D48") (class "Default")
      (node (ref "ARD_8") (pin "15") (pinfunction "15_15") (pintype "passive"))
    )
    (net (code "62") (name "D49") (class "Default")
      (node (ref "ARD_9") (pin "15") (pinfunction "15_15") (pintype "passive"))
    )
    (net (code "63") (name "D50") (class "Default")
      (node (ref "ARD_8") (pin "16") (pinfunction "16_16") (pintype "passive"))
    )
    (net (code "64") (name "D51") (class "Default")
      (node (ref "ARD_9") (pin "16") (pinfunction "16_16") (pintype "passive"))
    )
    (net (code "65") (name "D52") (class "Default")
      (node (ref "ARD_8") (pin "17") (pinfunction "17_17") (pintype "passive"))
    )
    (net (code "66") (name "D53") (class "Default")
      (node (ref "ARD_9") (pin "17") (pinfunction "17_17") (pintype "passive"))
    )
    (net (code "67") (name "DAC0") (class "Default")
      (node (ref "ARD_3") (pin "5") (pinfunction "5_5") (pintype "passive"))
    )
    (net (code "68") (name "DAC1") (class "Default")
      (node (ref "ARD_3") (pin "6") (pinfunction "6_6") (pintype "passive"))
    )
    (net (code "69") (name "FLT_CMP_TEMP") (class "Default")
      (node (ref "ARD_2") (pin "7") (pinfunction "7_7") (pintype "passive"))
      (node (ref "FLT_CMP_TEMP") (pin "1") (pinfunction "1_1") (pintype "passive"))
      (node (ref "R26") (pin "1") (pinfunction "1_1") (pintype "passive"))
      (node (ref "R27") (pin "2") (pinfunction "2_2") (pintype "passive"))
    )
    (net (code "70") (name "GND") (class "Default")
      (node (ref "ALT") (pin "3") (pinfunction "3_3") (pintype "passive"))
      (node (ref "ARD_1") (pin "6") (pinfunction "6_6") (pintype "passive"))
      (node (ref "ARD_1") (pin "7") (pinfunction "7_7") (pintype "passive"))
      (node (ref "ARD_4") (pin "6") (pinfunction "6_6") (pintype "passive"))
      (node (ref "ARD_7") (pin "4") (pinfunction "4_4") (pintype "passive"))
      (node (ref "ARD_8") (pin "18") (pinfunction "18_18") (pintype "passive"))
      (node (ref "ARD_9") (pin "18") (pinfunction "18_18") (pintype "passive"))
      (node (ref "B1CC") (pin "2") (pinfunction "2_2") (pintype "passive"))
      (node (ref "B2CC") (pin "2") (pinfunction "2_2") (pintype "passive"))
      (node (ref "BATT_EXT") (pin "NEG") (pinfunction "NEG_NEG") (pintype "bidirectional"))
      (node (ref "B_EXT") (pin "2") (pinfunction "S_2") (pintype "passive"))
      (node (ref "C1") (pin "2") (pinfunction "2_2") (pintype "passive"))
      (node (ref "C1_TLM") (pin "15") (pinfunction "15_15") (pintype "passive"))
      (node (ref "C1_TLM") (pin "2") (pinfunction "2_2") (pintype "passive"))
      (node (ref "C1_TLM") (pin "4") (pinfunction "4_4") (pintype "passive"))
      (node (ref "C2_PWR") (pin "2") (pinfunction "2_2") (pintype "passive"))
      (node (ref "C2_PWR") (pin "4") (pinfunction "4_4") (pintype "passive"))
      (node (ref "CN3") (pin "4") (pinfunction "4_4") (pintype "bidirectional"))
      (node (ref "FLT_CMP_TMP_NEG") (pin "1") (pinfunction "1_1") (pintype "passive"))
      (node (ref "GPS") (pin "7") (pinfunction "7_7") (pintype "passive"))
      (node (ref "LCC") (pin "2") (pinfunction "2_2") (pintype "passive"))
      (node (ref "Q1") (pin "E") (pinfunction "E_E") (pintype "passive"))
      (node (ref "Q2") (pin "E") (pinfunction "E_E") (pintype "passive"))
      (node (ref "Q3") (pin "E") (pinfunction "E_E") (pintype "passive"))
      (node (ref "Q4") (pin "E") (pinfunction "E_E") (pintype "passive"))
      (node (ref "Q5") (pin "E") (pinfunction "E_E") (pintype "passive"))
      (node (ref "Q6") (pin "E") (pinfunction "E_E") (pintype "passive"))
      (node (ref "Q7") (pin "E") (pinfunction "E_E") (pintype "passive"))
      (node (ref "R12") (pin "1") (pinfunction "1_1") (pintype "passive"))
      (node (ref "R13") (pin "1") (pinfunction "1_1") (pintype "passive"))
      (node (ref "R15") (pin "1") (pinfunction "1_1") (pintype "passive"))
      (node (ref "R18") (pin "1") (pinfunction "1_1") (pintype "passive"))
      (node (ref "R19") (pin "1") (pinfunction "1_1") (pintype "passive"))
      (node (ref "R23") (pin "1") (pinfunction "1_1") (pintype "passive"))
      (node (ref "R25") (pin "1") (pinfunction "1_1") (pintype "passive"))
      (node (ref "R27") (pin "1") (pinfunction "1_1") (pintype "passive"))
      (node (ref "R3") (pin "1") (pinfunction "1_1") (pintype "passive"))
      (node (ref "R31") (pin "1") (pinfunction "1_1") (pintype "passive"))
      (node (ref "R33") (pin "1") (pinfunction "1_1") (pintype "passive"))
      (node (ref "R36") (pin "1") (pinfunction "1_1") (pintype "passive"))
      (node (ref "R38") (pin "1") (pinfunction "1_1") (pintype "passive"))
      (node (ref "R8") (pin "1") (pinfunction "1_1") (pintype "passive"))
      (node (ref "R9") (pin "1") (pinfunction "1_1") (pintype "passive"))
      (node (ref "RB1") (pin "6") (pinfunction "6_6") (pintype "passive"))
      (node (ref "RB2") (pin "1") (pinfunction "1_1") (pintype "passive"))
      (node (ref "RB2") (pin "8") (pinfunction "8_8") (pintype "passive"))
      (node (ref "SACC") (pin "2") (pinfunction "2_2") (pintype "passive"))
      (node (ref "X1") (pin "2") (pinfunction "S_2") (pintype "passive"))
      (node (ref "X1") (pin "9") (pinfunction "S_9") (pintype "passive"))
      (node (ref "X2") (pin "10") (pinfunction "S_10") (pintype "passive"))
      (node (ref "X2") (pin "5") (pinfunction "S_5") (pintype "passive"))
      (node (ref "X2") (pin "8") (pinfunction "S_8") (pintype "passive"))
      (node (ref "X3") (pin "1") (pinfunction "1_1") (pintype "passive"))
    )
    (net (code "71") (name "GPS_EN") (class "Default")
      (node (ref "GPS") (pin "2") (pinfunction "2_2") (pintype "passive"))
    )
    (net (code "72") (name "GPS_FIX") (class "Default")
      (node (ref "GPS") (pin "4") (pinfunction "4_4") (pintype "passive"))
    )
    (net (code "73") (name "GPS_RX") (class "Default")
      (node (ref "GPS") (pin "6") (pinfunction "6_6") (pintype "passive"))
    )
    (net (code "74") (name "GPS_TX") (class "Default")
      (node (ref "GPS") (pin "5") (pinfunction "5_5") (pintype "passive"))
    )
    (net (code "75") (name "GPS_VBAT") (class "Default")
      (node (ref "GPS") (pin "3") (pinfunction "3_3") (pintype "passive"))
    )
    (net (code "76") (name "GYRO_PWR") (class "Default")
      (node (ref "ARD_8") (pin "5") (pinfunction "5_5") (pintype "passive"))
      (node (ref "CN3") (pin "3") (pinfunction "3_3") (pintype "bidirectional"))
    )
    (net (code "77") (name "HEATER_1_PWR") (class "Default")
      (node (ref "C3_CMD") (pin "8") (pinfunction "8_8") (pintype "passive"))
      (node (ref "PO4") (pin "1") (pinfunction "P_1") (pintype "passive"))
      (node (ref "X1") (pin "4") (pinfunction "S_4") (pintype "passive"))
    )
    (net (code "78") (name "HEATER_1_PWR_RTN") (class "Default")
      (node (ref "C3_CMD") (pin "9") (pinfunction "9_9") (pintype "passive"))
      (node (ref "Q4") (pin "C") (pinfunction "C_C") (pintype "passive"))
      (node (ref "X1") (pin "5") (pinfunction "S_5") (pintype "passive"))
    )
    (net (code "79") (name "HEATER_2_PWR") (class "Default")
      (node (ref "C3_CMD") (pin "10") (pinfunction "10_10") (pintype "passive"))
      (node (ref "PO5") (pin "1") (pinfunction "P_1") (pintype "passive"))
      (node (ref "X1") (pin "6") (pinfunction "S_6") (pintype "passive"))
    )
    (net (code "80") (name "HEATER_2_PWR_RTN") (class "Default")
      (node (ref "C3_CMD") (pin "11") (pinfunction "11_11") (pintype "passive"))
      (node (ref "Q5") (pin "C") (pinfunction "C_C") (pintype "passive"))
      (node (ref "X1") (pin "7") (pinfunction "S_7") (pintype "passive"))
    )
    (net (code "81") (name "HEATER_CONTROL_1") (class "Default")
      (node (ref "ARD_7") (pin "10") (pinfunction "10_10") (pintype "passive"))
      (node (ref "R10") (pin "2") (pinfunction "2_2") (pintype "passive"))
    )
    (net (code "82") (name "HEATER_CONTROL_2") (class "Default")
      (node (ref "ARD_6") (pin "3") (pinfunction "3_3") (pintype "passive"))
      (node (ref "R11") (pin "2") (pinfunction "2_2") (pintype "passive"))
    )
    (net (code "83") (name "IOREF") (class "Default")
      (node (ref "ARD_1") (pin "2") (pinfunction "2_2") (pintype "passive"))
    )
    (net (code "84") (name "LI_ION") (class "Default")
      (node (ref "RB2") (pin "7") (pinfunction "7_7") (pintype "passive"))
    )
    (net (code "85") (name "LOAD_IN") (class "Default")
      (node (ref "LCC") (pin "6") (pinfunction "6_6") (pintype "passive"))
      (node (ref "X2") (pin "9") (pinfunction "S_9") (pintype "passive"))
    )
    (net (code "86") (name "MISO") (class "Default")
      (node (ref "ARD_4") (pin "1") (pinfunction "1_1") (pintype "passive"))
      (node (ref "ARD_7") (pin "6") (pinfunction "6_6") (pintype "passive"))
    )
    (net (code "87") (name "MOSI") (class "Default")
      (node (ref "ARD_4") (pin "4") (pinfunction "4_4") (pintype "passive"))
      (node (ref "ARD_7") (pin "7") (pinfunction "7_7") (pintype "passive"))
    )
    (net (code "88") (name "NET_AV") (class "Default")
      (node (ref "RB2") (pin "5") (pinfunction "5_5") (pintype "passive"))
    )
    (net (code "89") (name "Net-(Q4-PadB)") (class "Default")
      (node (ref "Q4") (pin "B") (pinfunction "B_B") (pintype "passive"))
      (node (ref "R10") (pin "1") (pinfunction "1_1") (pintype "passive"))
      (node (ref "R12") (pin "2") (pinfunction "2_2") (pintype "passive"))
    )
    (net (code "90") (name "Net-(Q5-PadB)") (class "Default")
      (node (ref "Q5") (pin "B") (pinfunction "B_B") (pintype "passive"))
      (node (ref "R11") (pin "1") (pinfunction "1_1") (pintype "passive"))
      (node (ref "R13") (pin "2") (pinfunction "2_2") (pintype "passive"))
    )
    (net (code "91") (name "Net-(Q6-PadB)") (class "Default")
      (node (ref "Q6") (pin "B") (pinfunction "B_B") (pintype "passive"))
      (node (ref "R16") (pin "1") (pinfunction "1_1") (pintype "passive"))
      (node (ref "R18") (pin "2") (pinfunction "2_2") (pintype "passive"))
    )
    (net (code "92") (name "Net-(Q7-PadB)") (class "Default")
      (node (ref "Q7") (pin "B") (pinfunction "B_B") (pintype "passive"))
      (node (ref "R17") (pin "1") (pinfunction "1_1") (pintype "passive"))
      (node (ref "R19") (pin "2") (pinfunction "2_2") (pintype "passive"))
    )
    (net (code "93") (name "Net-(T1-B)") (class "Default")
      (node (ref "R1") (pin "1") (pinfunction "1_1") (pintype "passive"))
      (node (ref "R2") (pin "2") (pinfunction "2_2") (pintype "passive"))
      (node (ref "T1") (pin "2") (pinfunction "B_2") (pintype "passive"))
    )
    (net (code "94") (name "Net-(T1-E)") (class "Default")
      (node (ref "Q1") (pin "B") (pinfunction "B_B") (pintype "passive"))
      (node (ref "R2") (pin "1") (pinfunction "1_1") (pintype "passive"))
      (node (ref "R3") (pin "2") (pinfunction "2_2") (pintype "passive"))
      (node (ref "T1") (pin "3") (pinfunction "E_3") (pintype "passive"))
    )
    (net (code "95") (name "Net-(T2-B)") (class "Default")
      (node (ref "R4") (pin "1") (pinfunction "1_1") (pintype "passive"))
      (node (ref "R6") (pin "2") (pinfunction "2_2") (pintype "passive"))
      (node (ref "T2") (pin "2") (pinfunction "B_2") (pintype "passive"))
    )
    (net (code "96") (name "Net-(T2-E)") (class "Default")
      (node (ref "Q2") (pin "B") (pinfunction "B_B") (pintype "passive"))
      (node (ref "R6") (pin "1") (pinfunction "1_1") (pintype "passive"))
      (node (ref "R8") (pin "2") (pinfunction "2_2") (pintype "passive"))
      (node (ref "T2") (pin "3") (pinfunction "E_3") (pintype "passive"))
    )
    (net (code "97") (name "Net-(T3-B)") (class "Default")
      (node (ref "R5") (pin "1") (pinfunction "1_1") (pintype "passive"))
      (node (ref "R7") (pin "2") (pinfunction "2_2") (pintype "passive"))
      (node (ref "T3") (pin "2") (pinfunction "B_2") (pintype "passive"))
    )
    (net (code "98") (name "Net-(T3-E)") (class "Default")
      (node (ref "Q3") (pin "B") (pinfunction "B_B") (pintype "passive"))
      (node (ref "R7") (pin "1") (pinfunction "1_1") (pintype "passive"))
      (node (ref "R9") (pin "2") (pinfunction "2_2") (pintype "passive"))
      (node (ref "T3") (pin "3") (pinfunction "E_3") (pintype "passive"))
    )
    (net (code "99") (name "ON_OFF") (class "Default")
      (node (ref "RB2") (pin "6") (pinfunction "6_6") (pintype "passive"))
    )
    (net (code "100") (name "PYRO_1_PWR") (class "Default")
      (node (ref "C3_CMD") (pin "1") (pinfunction "1_1") (pintype "passive"))
      (node (ref "PO1") (pin "1") (pinfunction "P_1") (pintype "passive"))
    )
    (net (code "101") (name "PYRO_1_PWR_RTN") (class "Default")
      (node (ref "C3_CMD") (pin "2") (pinfunction "2_2") (pintype "passive"))
      (node (ref "Q1") (pin "C") (pinfunction "C_C") (pintype "passive"))
      (node (ref "T1") (pin "1") (pinfunction "C_1") (pintype "passive"))
    )
    (net (code "102") (name "PYRO_2_PWR") (class "Default")
      (node (ref "C3_CMD") (pin "3") (pinfunction "3_3") (pintype "passive"))
      (node (ref "PO2") (pin "1") (pinfunction "P_1") (pintype "passive"))
    )
    (net (code "103") (name "PYRO_2_PWR_RTN") (class "Default")
      (node (ref "C3_CMD") (pin "4") (pinfunction "4_4") (pintype "passive"))
      (node (ref "Q2") (pin "C") (pinfunction "C_C") (pintype "passive"))
      (node (ref "T2") (pin "1") (pinfunction "C_1") (pintype "passive"))
    )
    (net (code "104") (name "RESET") (class "Default")
      (node (ref "ARD_1") (pin "3") (pinfunction "3_3") (pintype "passive"))
      (node (ref "ARD_4") (pin "5") (pinfunction "5_5") (pintype "passive"))
    )
    (net (code "105") (name "RI") (class "Default")
      (node (ref "RB2") (pin "4") (pinfunction "4_4") (pintype "passive"))
    )
    (net (code "106") (name "RTS") (class "Default")
      (node (ref "RB1") (pin "1") (pinfunction "1_1") (pintype "passive"))
    )
    (net (code "107") (name "RX0") (class "Default")
      (node (ref "ARD_6") (pin "8") (pinfunction "8_8") (pintype "passive"))
      (node (ref "X3") (pin "2") (pinfunction "2_2") (pintype "passive"))
    )
    (net (code "108") (name "RX1") (class "Default")
      (node (ref "ARD_5") (pin "6") (pinfunction "6_6") (pintype "passive"))
    )
    (net (code "109") (name "RX2") (class "Default")
      (node (ref "ARD_5") (pin "4") (pinfunction "4_4") (pintype "passive"))
    )
    (net (code "110") (name "RX3") (class "Default")
      (node (ref "ARD_5") (pin "2") (pinfunction "2_2") (pintype "passive"))
      (node (ref "RB1") (pin "2") (pinfunction "2_2") (pintype "passive"))
    )
    (net (code "111") (name "SCK") (class "Default")
      (node (ref "ARD_4") (pin "3") (pinfunction "3_3") (pintype "passive"))
      (node (ref "ARD_7") (pin "5") (pinfunction "5_5") (pintype "passive"))
    )
    (net (code "112") (name "SCL") (class "Default")
      (node (ref "ARD_5") (pin "8") (pinfunction "8_8") (pintype "passive"))
      (node (ref "B1CC") (pin "3") (pinfunction "3_3") (pintype "passive"))
      (node (ref "B2CC") (pin "3") (pinfunction "3_3") (pintype "passive"))
      (node (ref "CN3") (pin "1") (pinfunction "1_1") (pintype "bidirectional"))
      (node (ref "LCC") (pin "3") (pinfunction "3_3") (pintype "passive"))
      (node (ref "SACC") (pin "3") (pinfunction "3_3") (pintype "passive"))
    )
    (net (code "113") (name "SCL1") (class "Default")
      (node (ref "ARD_7") (pin "1") (pinfunction "1_1") (pintype "passive"))
    )
    (net (code "114") (name "SDA") (class "Default")
      (node (ref "ARD_5") (pin "7") (pinfunction "7_7") (pintype "passive"))
      (node (ref "B1CC") (pin "4") (pinfunction "4_4") (pintype "passive"))
      (node (ref "B2CC") (pin "4") (pinfunction "4_4") (pintype "passive"))
      (node (ref "CN3") (pin "2") (pinfunction "2_2") (pintype "bidirectional"))
      (node (ref "LCC") (pin "4") (pinfunction "4_4") (pintype "passive"))
      (node (ref "SACC") (pin "4") (pinfunction "4_4") (pintype "passive"))
    )
    (net (code "115") (name "SDA1") (class "Default")
      (node (ref "ARD_7") (pin "2") (pinfunction "2_2") (pintype "passive"))
    )
    (net (code "116") (name "SPARE_1_PWR") (class "Default")
      (node (ref "C3_CMD") (pin "12") (pinfunction "12_12") (pintype "passive"))
      (node (ref "PO6") (pin "1") (pinfunction "P_1") (pintype "passive"))
      (node (ref "SPRL1") (pin "1") (pinfunction "S_1") (pintype "passive"))
    )
    (net (code "117") (name "SPARE_1_PWR_RTN") (class "Default")
      (node (ref "C3_CMD") (pin "13") (pinfunction "13_13") (pintype "passive"))
      (node (ref "Q6") (pin "C") (pinfunction "C_C") (pintype "passive"))
    )
    (net (code "118") (name "SPARE_HIGH_1_CONTROL") (class "Default")
      (node (ref "ARD_9") (pin "2") (pinfunction "2_2") (pintype "passive"))
      (node (ref "R5") (pin "2") (pinfunction "2_2") (pintype "passive"))
    )
    (net (code "119") (name "SPARE_HIGH_1_PWR") (class "Default")
      (node (ref "C3_CMD") (pin "5") (pinfunction "5_5") (pintype "passive"))
      (node (ref "PO3") (pin "1") (pinfunction "P_1") (pintype "passive"))
      (node (ref "SPRH1") (pin "1") (pinfunction "S_1") (pintype "passive"))
    )
    (net (code "120") (name "SPARE_HIGH_1_PWR_RTN") (class "Default")
      (node (ref "C3_CMD") (pin "6") (pinfunction "6_6") (pintype "passive"))
      (node (ref "Q3") (pin "C") (pinfunction "C_C") (pintype "passive"))
      (node (ref "T3") (pin "1") (pinfunction "C_1") (pintype "passive"))
    )
    (net (code "121") (name "SPARE_LOW_1_CONTROL") (class "Default")
      (node (ref "ARD_9") (pin "3") (pinfunction "3_3") (pintype "passive"))
      (node (ref "R16") (pin "2") (pinfunction "2_2") (pintype "passive"))
    )
    (net (code "122") (name "S{slash}A_PWR_IN") (class "Default")
      (node (ref "C2_PWR") (pin "10") (pinfunction "10_10") (pintype "passive"))
      (node (ref "C2_PWR") (pin "6") (pinfunction "6_6") (pintype "passive"))
      (node (ref "C2_PWR") (pin "8") (pinfunction "8_8") (pintype "passive"))
      (node (ref "SACC") (pin "6") (pinfunction "6_6") (pintype "passive"))
    )
    (net (code "123") (name "S{slash}A_PWR_OUT") (class "Default")
      (node (ref "SACC") (pin "5") (pinfunction "5_5") (pintype "passive"))
      (node (ref "X2") (pin "1") (pinfunction "S_1") (pintype "passive"))
    )
    (net (code "124") (name "S{slash}A_PWR_OUT_RTN") (class "Default")
      (node (ref "X2") (pin "2") (pinfunction "S_2") (pintype "passive"))
    )
    (net (code "125") (name "S{slash}A_PWR_RTN") (class "Default")
      (node (ref "C2_PWR") (pin "11") (pinfunction "11_11") (pintype "passive"))
      (node (ref "C2_PWR") (pin "7") (pinfunction "7_7") (pintype "passive"))
      (node (ref "C2_PWR") (pin "9") (pinfunction "9_9") (pintype "passive"))
    )
    (net (code "126") (name "TEMP_EXT_1") (class "Default")
      (node (ref "ARD_2") (pin "8") (pinfunction "8_8") (pintype "passive"))
      (node (ref "C1_TLM") (pin "1") (pinfunction "1_1") (pintype "passive"))
      (node (ref "R22") (pin "1") (pinfunction "1_1") (pintype "passive"))
      (node (ref "R23") (pin "2") (pinfunction "2_2") (pintype "passive"))
    )
    (net (code "127") (name "TEMP_EXT_2") (class "Default")
      (node (ref "ARD_2") (pin "6") (pinfunction "6_6") (pintype "passive"))
      (node (ref "C1_TLM") (pin "3") (pinfunction "3_3") (pintype "passive"))
      (node (ref "R24") (pin "1") (pinfunction "1_1") (pintype "passive"))
      (node (ref "R25") (pin "2") (pinfunction "2_2") (pintype "passive"))
    )
    (net (code "128") (name "TX0") (class "Default")
      (node (ref "ARD_6") (pin "7") (pinfunction "7_7") (pintype "passive"))
      (node (ref "X3") (pin "3") (pinfunction "3_3") (pintype "passive"))
    )
    (net (code "129") (name "TX1") (class "Default")
      (node (ref "ARD_5") (pin "5") (pinfunction "5_5") (pintype "passive"))
    )
    (net (code "130") (name "TX2") (class "Default")
      (node (ref "ARD_5") (pin "3") (pinfunction "3_3") (pintype "passive"))
    )
    (net (code "131") (name "TX3") (class "Default")
      (node (ref "ARD_5") (pin "1") (pinfunction "1_1") (pintype "passive"))
      (node (ref "RB1") (pin "3") (pinfunction "3_3") (pintype "passive"))
    )
    (net (code "132") (name "UNKNOWN") (class "Default")
      (node (ref "ARD_1") (pin "1") (pinfunction "1_1") (pintype "passive"))
    )
    (net (code "133") (name "VCC_RB") (class "Default")
      (node (ref "RB1") (pin "4") (pinfunction "4_4") (pintype "passive"))
    )
    (net (code "134") (name "VIN") (class "Default")
      (node (ref "ARD_1") (pin "8") (pinfunction "8_8") (pintype "passive"))
      (node (ref "GPS") (pin "8") (pinfunction "8_8") (pintype "passive"))
      (node (ref "LCC") (pin "5") (pinfunction "5_5") (pintype "passive"))
      (node (ref "PVIN1") (pin "1") (pinfunction "P_1") (pintype "passive"))
      (node (ref "PVIN2") (pin "1") (pinfunction "P_1") (pintype "passive"))
      (node (ref "PVIN3") (pin "1") (pinfunction "P_1") (pintype "passive"))
      (node (ref "PVIN4") (pin "1") (pinfunction "P_1") (pintype "passive"))
      (node (ref "PVIN5") (pin "1") (pinfunction "P_1") (pintype "passive"))
      (node (ref "PVIN6") (pin "1") (pinfunction "P_1") (pintype "passive"))
      (node (ref "PVIN7") (pin "1") (pinfunction "P_1") (pintype "passive"))
      (node (ref "R14") (pin "2") (pinfunction "2_2") (pintype "passive"))
    )
    (net (code "135") (name "VIN_VOLTAGE_TLM") (class "Default")
      (node (ref "ARD_2") (pin "4") (pinfunction "4_4") (pintype "passive"))
      (node (ref "C1") (pin "1") (pinfunction "1_1") (pintype "passive"))
      (node (ref "R14") (pin "1") (pinfunction "1_1") (pintype "passive"))
      (node (ref "R15") (pin "2") (pinfunction "2_2") (pintype "passive"))
    )
    (net (code "136") (name "unconnected-(ALT-Pad8)") (class "Default")
      (node (ref "ALT") (pin "8") (pinfunction "8_8") (pintype "passive"))
    )
    (net (code "137") (name "unconnected-(C1_TLM-Pad5)") (class "Default")
      (node (ref "C1_TLM") (pin "5") (pinfunction "5_5") (pintype "passive"))
    )
    (net (code "138") (name "unconnected-(C2_PWR-Pad5)") (class "Default")
      (node (ref "C2_PWR") (pin "5") (pinfunction "5_5") (pintype "passive"))
    )
    (net (code "139") (name "unconnected-(C2_PWR-Pad12)") (class "Default")
      (node (ref "C2_PWR") (pin "12") (pinfunction "12_12") (pintype "passive"))
    )
    (net (code "140") (name "unconnected-(C2_PWR-Pad13)") (class "Default")
      (node (ref "C2_PWR") (pin "13") (pinfunction "13_13") (pintype "passive"))
    )
    (net (code "141") (name "unconnected-(C2_PWR-Pad14)") (class "Default")
      (node (ref "C2_PWR") (pin "14") (pinfunction "14_14") (pintype "passive"))
    )
    (net (code "142") (name "unconnected-(C2_PWR-Pad15)") (class "Default")
      (node (ref "C2_PWR") (pin "15") (pinfunction "15_15") (pintype "passive"))
    )
    (net (code "143") (name "unconnected-(C3_CMD-Pad7)") (class "Default")
      (node (ref "C3_CMD") (pin "7") (pinfunction "7_7") (pintype "passive"))
    )
    (net (code "144") (name "unconnected-(IC1-+IN-Pad3)") (class "Default")
      (node (ref "IC1") (pin "3") (pinfunction "+IN_3") (pintype "input"))
    )
    (net (code "145") (name "unconnected-(IC1--IN-Pad2)") (class "Default")
      (node (ref "IC1") (pin "2") (pinfunction "-IN_2") (pintype "input"))
    )
    (net (code "146") (name "unconnected-(IC1-BYPASS-Pad7)") (class "Default")
      (node (ref "IC1") (pin "7") (pinfunction "BYPASS_7") (pintype "passive"))
    )
    (net (code "147") (name "unconnected-(IC1-GAIN-Pad1)") (class "Default")
      (node (ref "IC1") (pin "1") (pinfunction "GAIN_1") (pintype "passive"))
    )
  )
)
